# Sensor_Speed.net
KiCad netlist of a schematic drawn in Altium Designer
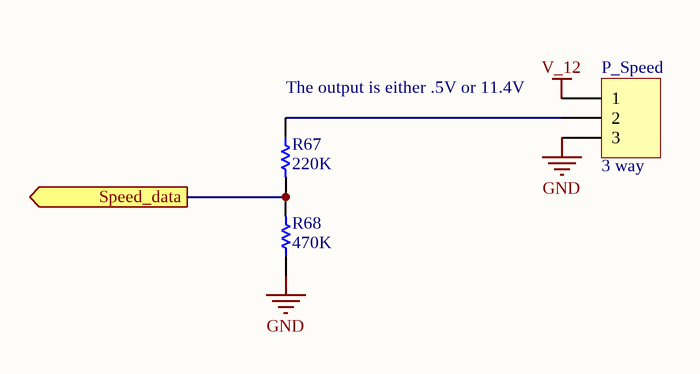
[diagram p0: Sensor_Speed.SchDoc]

(export (version "E")
  (design (tool "Eeschema 10.0.6"))
  (components
    (comp (ref "P_Speed")
      (value "3 way")
      (footprint "Con_3way_0.1")
      (description "3 way upright Locking & Polarising Header Connector")
      (fields (field (name "PART NUMBER") "Con3ra100ml"))
      (libsource (lib "ECE_Component_Library_2") (part "Con3ra100ml"))
    )
    (comp (ref "R67")
      (value "220K")
      (footprint "R0603")
      (description "0603 Resistor")
      (fields (field (name "PART NUMBER") "220K_R0603"))
      (libsource (lib "ECE_Component_Library_2") (part "220K_R0603"))
    )
    (comp (ref "R68")
      (value "470K")
      (footprint "R0603")
      (description "0603 Resistor")
      (fields (field (name "PART NUMBER") "470K_R0603"))
      (libsource (lib "ECE_Component_Library_2") (part "470K_R0603"))
    )
  )
  (nets
    (net (code "1") (name "/Speed_data") (class "Default")
      (node (ref "R67") (pin "2") (pinfunction "2_2") (pintype "passive"))
      (node (ref "R68") (pin "2") (pinfunction "2_2") (pintype "passive"))
    )
    (net (code "2") (name "GND") (class "Default")
      (node (ref "P_Speed") (pin "3") (pinfunction "3_3") (pintype "passive"))
      (node (ref "R68") (pin "1") (pinfunction "1_1") (pintype "passive"))
    )
    (net (code "3") (name "Net-(P_Speed-Pad2)") (class "Default")
      (node (ref "P_Speed") (pin "2") (pinfunction "2_2") (pintype "passive"))
      (node (ref "R67") (pin "1") (pinfunction "1_1") (pintype "passive"))
    )
    (net (code "4") (name "V_12") (class "Default")
      (node (ref "P_Speed") (pin "1") (pinfunction "1_1") (pintype "passive"))
    )
  )
)
